# CS301_YOURGROUPNUM.net
KiCad netlist of a schematic drawn in Altium Designer
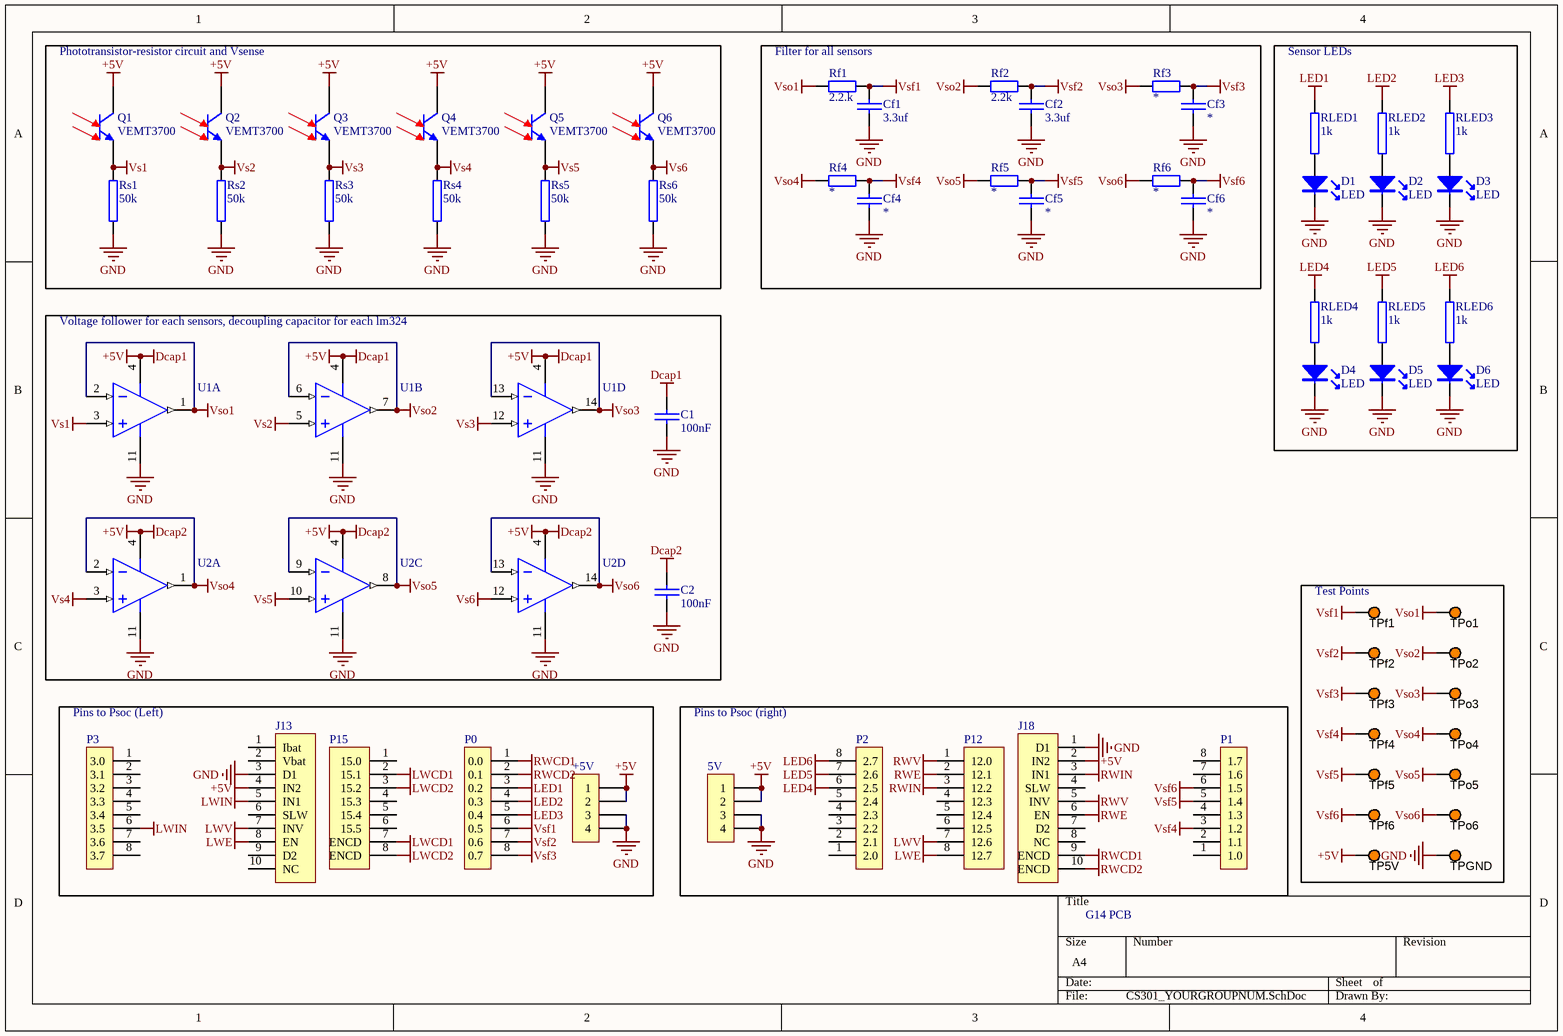
[diagram p0: CS301_YOURGROUPNUM.SchDoc]

(export (version "E")
  (design (tool "Eeschema 10.0.6"))
  (components
    (comp (ref "+5V")
      (value "5V")
      (footprint "IDC4")
      (description "Connector")
      (libsource (lib "Miscellaneous Devices") (part "CON4"))
    )
    (comp (ref "5V")
      (value "5V")
      (footprint "IDC4")
      (description "Connector")
      (libsource (lib "Miscellaneous Devices") (part "CON4"))
    )
    (comp (ref "C1")
      (value "100nF")
      (footprint "CCAP-5P0")
      (description "TH ceramic capacitor with 5mm pitch")
      (libsource (lib "EE209_SchLib") (part "CerCap_TH_5P0"))
    )
    (comp (ref "C2")
      (value "100nF")
      (footprint "CCAP-5P0")
      (description "TH ceramic capacitor with 5mm pitch")
      (libsource (lib "EE209_SchLib") (part "CerCap_TH_5P0"))
    )
    (comp (ref "Cf1")
      (value "3.3uf")
      (footprint "CCAP-5P0")
      (description "TH ceramic capacitor with 5mm pitch")
      (libsource (lib "EE209_SchLib") (part "CerCap_TH_5P0"))
    )
    (comp (ref "Cf2")
      (value "3.3uf")
      (footprint "CCAP-5P0")
      (description "TH ceramic capacitor with 5mm pitch")
      (libsource (lib "EE209_SchLib") (part "CerCap_TH_5P0"))
    )
    (comp (ref "Cf3")
      (value "*")
      (footprint "CCAP-5P0")
      (description "TH ceramic capacitor with 5mm pitch")
      (libsource (lib "EE209_SchLib") (part "CerCap_TH_5P0"))
    )
    (comp (ref "Cf4")
      (value "*")
      (footprint "CCAP-5P0")
      (description "TH ceramic capacitor with 5mm pitch")
      (libsource (lib "EE209_SchLib") (part "CerCap_TH_5P0"))
    )
    (comp (ref "Cf5")
      (value "*")
      (footprint "CCAP-5P0")
      (description "TH ceramic capacitor with 5mm pitch")
      (libsource (lib "EE209_SchLib") (part "CerCap_TH_5P0"))
    )
    (comp (ref "Cf6")
      (value "*")
      (footprint "CCAP-5P0")
      (description "TH ceramic capacitor with 5mm pitch")
      (libsource (lib "EE209_SchLib") (part "CerCap_TH_5P0"))
    )
    (comp (ref "D1") (value "LED") (footprint "LED0.1/5MM") (libsource (lib "COMSYS301") (part "LED")))
    (comp (ref "D2") (value "LED") (footprint "LED0.1/5MM") (libsource (lib "COMSYS301") (part "LED")))
    (comp (ref "D3") (value "LED") (footprint "LED0.1/5MM") (libsource (lib "COMSYS301") (part "LED")))
    (comp (ref "D4") (value "LED") (footprint "LED0.1/5MM") (libsource (lib "COMSYS301") (part "LED")))
    (comp (ref "D5") (value "LED") (footprint "LED0.1/5MM") (libsource (lib "COMSYS301") (part "LED")))
    (comp (ref "D6") (value "LED") (footprint "LED0.1/5MM") (libsource (lib "COMSYS301") (part "LED")))
    (comp (ref "J13")
      (value "CON10")
      (footprint "idc10")
      (description "Connector")
      (libsource (lib "Miscellaneous Devices") (part "CON10"))
    )
    (comp (ref "J18")
      (value "CON10")
      (footprint "IDC10")
      (description "Connector")
      (libsource (lib "") (part "CON10_1"))
    )
    (comp (ref "P0")
      (value "P0")
      (footprint "idc8")
      (description "Connector")
      (libsource (lib "") (part "CON8_1"))
    )
    (comp (ref "P1")
      (value "P1")
      (footprint "idc8")
      (description "Connector")
      (libsource (lib "") (part "CON8_2"))
    )
    (comp (ref "P2")
      (value "P2")
      (footprint "idc8")
      (description "Connector")
      (libsource (lib "") (part "CON8_2"))
    )
    (comp (ref "P3")
      (value "P3")
      (footprint "idc8")
      (description "Connector")
      (libsource (lib "Miscellaneous Devices") (part "CON8"))
    )
    (comp (ref "P12")
      (value "P12")
      (footprint "idc8")
      (description "Connector")
      (libsource (lib "Miscellaneous Devices") (part "CON8_1"))
    )
    (comp (ref "P15")
      (value "P15")
      (footprint "idc8")
      (description "Connector")
      (libsource (lib "") (part "CON8_1_1"))
    )
    (comp (ref "Q1")
      (value "VEMT3700")
      (footprint "VEMT3700")
      (description "Silicon NPN Phototransistor")
      (libsource (lib "COMSYS301") (part "VEMT3700"))
    )
    (comp (ref "Q2")
      (value "VEMT3700")
      (footprint "VEMT3700")
      (description "Silicon NPN Phototransistor")
      (libsource (lib "COMSYS301") (part "VEMT3700"))
    )
    (comp (ref "Q3")
      (value "VEMT3700")
      (footprint "VEMT3700")
      (description "Silicon NPN Phototransistor")
      (libsource (lib "COMSYS301") (part "VEMT3700"))
    )
    (comp (ref "Q4")
      (value "VEMT3700")
      (footprint "VEMT3700")
      (description "Silicon NPN Phototransistor")
      (libsource (lib "COMSYS301") (part "VEMT3700"))
    )
    (comp (ref "Q5")
      (value "VEMT3700")
      (footprint "VEMT3700")
      (description "Silicon NPN Phototransistor")
      (libsource (lib "COMSYS301") (part "VEMT3700"))
    )
    (comp (ref "Q6")
      (value "VEMT3700")
      (footprint "VEMT3700")
      (description "Silicon NPN Phototransistor")
      (libsource (lib "COMSYS301") (part "VEMT3700"))
    )
    (comp (ref "Rf1")
      (value "2.2.k")
      (footprint "AXIAL-0.4")
      (description "Through hole resistor")
      (fields (field (name "PUBLISHER") "Altium Limited"))
      (libsource (lib "EE209_SchLib") (part "Res_TH_0AX4"))
    )
    (comp (ref "Rf2")
      (value "2.2k")
      (footprint "AXIAL-0.4")
      (description "Through hole resistor")
      (fields (field (name "PUBLISHER") "Altium Limited"))
      (libsource (lib "EE209_SchLib") (part "Res_TH_0AX4"))
    )
    (comp (ref "Rf3")
      (value "*")
      (footprint "AXIAL-0.4")
      (description "Through hole resistor")
      (fields (field (name "PUBLISHER") "Altium Limited"))
      (libsource (lib "EE209_SchLib") (part "Res_TH_0AX4"))
    )
    (comp (ref "Rf4")
      (value "*")
      (footprint "AXIAL-0.4")
      (description "Through hole resistor")
      (fields (field (name "PUBLISHER") "Altium Limited"))
      (libsource (lib "EE209_SchLib") (part "Res_TH_0AX4"))
    )
    (comp (ref "Rf5")
      (value "*")
      (footprint "AXIAL-0.4")
      (description "Through hole resistor")
      (fields (field (name "PUBLISHER") "Altium Limited"))
      (libsource (lib "EE209_SchLib") (part "Res_TH_0AX4"))
    )
    (comp (ref "Rf6")
      (value "*")
      (footprint "AXIAL-0.4")
      (description "Through hole resistor")
      (fields (field (name "PUBLISHER") "Altium Limited"))
      (libsource (lib "EE209_SchLib") (part "Res_TH_0AX4"))
    )
    (comp (ref "RLED1") (value "1k") (footprint "AXIAL0.4") (libsource (lib "COMSYS301") (part "RES2")))
    (comp (ref "RLED2") (value "1k") (footprint "AXIAL0.4") (libsource (lib "COMSYS301") (part "RES2")))
    (comp (ref "RLED3") (value "1k") (footprint "AXIAL0.4") (libsource (lib "COMSYS301") (part "RES2")))
    (comp (ref "RLED4") (value "1k") (footprint "AXIAL0.4") (libsource (lib "COMSYS301") (part "RES2")))
    (comp (ref "RLED5") (value "1k") (footprint "AXIAL0.4") (libsource (lib "COMSYS301") (part "RES2")))
    (comp (ref "RLED6") (value "1k") (footprint "AXIAL0.4") (libsource (lib "COMSYS301") (part "RES2")))
    (comp (ref "Rs1") (value "50k") (footprint "AXIAL0.4") (libsource (lib "COMSYS301") (part "RES2")))
    (comp (ref "Rs2") (value "50k") (footprint "AXIAL0.4") (libsource (lib "COMSYS301") (part "RES2")))
    (comp (ref "Rs3") (value "50k") (footprint "AXIAL0.4") (libsource (lib "COMSYS301") (part "RES2")))
    (comp (ref "Rs4") (value "50k") (footprint "AXIAL0.4") (libsource (lib "COMSYS301") (part "RES2")))
    (comp (ref "Rs5") (value "50k") (footprint "AXIAL0.4") (libsource (lib "COMSYS301") (part "RES2")))
    (comp (ref "Rs6") (value "50k") (footprint "AXIAL0.4") (libsource (lib "COMSYS301") (part "RES2")))
    (comp (ref "TP5V")
      (value "5003")
      (footprint "EE209_PcbLib:TP_TH")
      (description "Test Point, Orange, 1-Pin THD, RoHS")
      (libsource (lib "EE209_SchLib") (part "TestPoint"))
    )
    (comp (ref "TPf1")
      (value "5003")
      (footprint "EE209_PcbLib:TP_TH")
      (description "Test Point, Orange, 1-Pin THD, RoHS")
      (libsource (lib "EE209_SchLib") (part "TestPoint"))
    )
    (comp (ref "TPf2")
      (value "5003")
      (footprint "EE209_PcbLib:TP_TH")
      (description "Test Point, Orange, 1-Pin THD, RoHS")
      (libsource (lib "EE209_SchLib") (part "TestPoint"))
    )
    (comp (ref "TPf3")
      (value "5003")
      (footprint "EE209_PcbLib:TP_TH")
      (description "Test Point, Orange, 1-Pin THD, RoHS")
      (libsource (lib "EE209_SchLib") (part "TestPoint"))
    )
    (comp (ref "TPf4")
      (value "5003")
      (footprint "EE209_PcbLib:TP_TH")
      (description "Test Point, Orange, 1-Pin THD, RoHS")
      (libsource (lib "EE209_SchLib") (part "TestPoint"))
    )
    (comp (ref "TPf5")
      (value "5003")
      (footprint "EE209_PcbLib:TP_TH")
      (description "Test Point, Orange, 1-Pin THD, RoHS")
      (libsource (lib "EE209_SchLib") (part "TestPoint"))
    )
    (comp (ref "TPf6")
      (value "5003")
      (footprint "EE209_PcbLib:TP_TH")
      (description "Test Point, Orange, 1-Pin THD, RoHS")
      (libsource (lib "EE209_SchLib") (part "TestPoint"))
    )
    (comp (ref "TPGND")
      (value "5003")
      (footprint "EE209_PcbLib:TP_TH")
      (description "Test Point, Orange, 1-Pin THD, RoHS")
      (libsource (lib "EE209_SchLib") (part "TestPoint"))
    )
    (comp (ref "TPo1")
      (value "5003")
      (footprint "EE209_PcbLib:TP_TH")
      (description "Test Point, Orange, 1-Pin THD, RoHS")
      (libsource (lib "EE209_SchLib") (part "TestPoint"))
    )
    (comp (ref "TPo2")
      (value "5003")
      (footprint "EE209_PcbLib:TP_TH")
      (description "Test Point, Orange, 1-Pin THD, RoHS")
      (libsource (lib "EE209_SchLib") (part "TestPoint"))
    )
    (comp (ref "TPo3")
      (value "5003")
      (footprint "EE209_PcbLib:TP_TH")
      (description "Test Point, Orange, 1-Pin THD, RoHS")
      (libsource (lib "EE209_SchLib") (part "TestPoint"))
    )
    (comp (ref "TPo4")
      (value "5003")
      (footprint "EE209_PcbLib:TP_TH")
      (description "Test Point, Orange, 1-Pin THD, RoHS")
      (libsource (lib "EE209_SchLib") (part "TestPoint"))
    )
    (comp (ref "TPo5")
      (value "5003")
      (footprint "EE209_PcbLib:TP_TH")
      (description "Test Point, Orange, 1-Pin THD, RoHS")
      (libsource (lib "EE209_SchLib") (part "TestPoint"))
    )
    (comp (ref "TPo6")
      (value "5003")
      (footprint "EE209_PcbLib:TP_TH")
      (description "Test Point, Orange, 1-Pin THD, RoHS")
      (libsource (lib "EE209_SchLib") (part "TestPoint"))
    )
    (comp (ref "U1")
      (value "LM324")
      (footprint "DIP-14")
      (description "IC OPAMP GP 14DIP")
      (fields
        (field (name "MANUFACTURER") "ON Semiconductor")
        (field (name "MANUFACTURER PART NUMBER") "LM324N")
      )
      (libsource (lib "EE209_SchLib") (part "LM324N_TH_DIP16"))
    )
    (comp (ref "U2")
      (value "LM324")
      (footprint "DIP-14")
      (description "IC OPAMP GP 14DIP")
      (fields
        (field (name "MANUFACTURER") "ON Semiconductor")
        (field (name "MANUFACTURER PART NUMBER") "LM324N")
      )
      (libsource (lib "EE209_SchLib") (part "LM324N_TH_DIP16"))
    )
  )
  (nets
    (net (code "1") (name "+5V") (class "Default")
      (node (ref "+5V") (pin "1") (pinfunction "1_1") (pintype "passive"))
      (node (ref "+5V") (pin "2") (pinfunction "2_2") (pintype "passive"))
      (node (ref "5V") (pin "1") (pinfunction "1_1") (pintype "passive"))
      (node (ref "5V") (pin "2") (pinfunction "2_2") (pintype "passive"))
      (node (ref "C1") (pin "1") (pinfunction "1_1") (pintype "passive"))
      (node (ref "C2") (pin "1") (pinfunction "1_1") (pintype "passive"))
      (node (ref "J13") (pin "4") (pinfunction "IN2_4") (pintype "passive"))
      (node (ref "J18") (pin "2") (pinfunction "IN2_2") (pintype "passive"))
      (node (ref "Q1") (pin "1") (pinfunction "C_1") (pintype "passive"))
      (node (ref "Q2") (pin "1") (pinfunction "C_1") (pintype "passive"))
      (node (ref "Q3") (pin "1") (pinfunction "C_1") (pintype "passive"))
      (node (ref "Q4") (pin "1") (pinfunction "C_1") (pintype "passive"))
      (node (ref "Q5") (pin "1") (pinfunction "C_1") (pintype "passive"))
      (node (ref "Q6") (pin "1") (pinfunction "C_1") (pintype "passive"))
      (node (ref "TP5V") (pin "1") (pinfunction "1_1") (pintype "passive"))
      (node (ref "U1") (pin "4") (pinfunction "VDD_4") (pintype "power_in"))
      (node (ref "U2") (pin "4") (pinfunction "VDD_4") (pintype "power_in"))
    )
    (net (code "2") (name "GND") (class "Default")
      (node (ref "+5V") (pin "3") (pinfunction "3_3") (pintype "passive"))
      (node (ref "+5V") (pin "4") (pinfunction "4_4") (pintype "passive"))
      (node (ref "5V") (pin "3") (pinfunction "3_3") (pintype "passive"))
      (node (ref "5V") (pin "4") (pinfunction "4_4") (pintype "passive"))
      (node (ref "C1") (pin "2") (pinfunction "2_2") (pintype "passive"))
      (node (ref "C2") (pin "2") (pinfunction "2_2") (pintype "passive"))
      (node (ref "Cf1") (pin "2") (pinfunction "2_2") (pintype "passive"))
      (node (ref "Cf2") (pin "2") (pinfunction "2_2") (pintype "passive"))
      (node (ref "Cf3") (pin "2") (pinfunction "2_2") (pintype "passive"))
      (node (ref "Cf4") (pin "2") (pinfunction "2_2") (pintype "passive"))
      (node (ref "Cf5") (pin "2") (pinfunction "2_2") (pintype "passive"))
      (node (ref "Cf6") (pin "2") (pinfunction "2_2") (pintype "passive"))
      (node (ref "D1") (pin "K") (pinfunction "2_K") (pintype "passive"))
      (node (ref "D2") (pin "K") (pinfunction "2_K") (pintype "passive"))
      (node (ref "D3") (pin "K") (pinfunction "2_K") (pintype "passive"))
      (node (ref "D4") (pin "K") (pinfunction "2_K") (pintype "passive"))
      (node (ref "D5") (pin "K") (pinfunction "2_K") (pintype "passive"))
      (node (ref "D6") (pin "K") (pinfunction "2_K") (pintype "passive"))
      (node (ref "J13") (pin "3") (pinfunction "D1_3") (pintype "passive"))
      (node (ref "J18") (pin "1") (pinfunction "D1_1") (pintype "passive"))
      (node (ref "Rs1") (pin "2") (pinfunction "2_2") (pintype "passive"))
      (node (ref "Rs2") (pin "2") (pinfunction "2_2") (pintype "passive"))
      (node (ref "Rs3") (pin "2") (pinfunction "2_2") (pintype "passive"))
      (node (ref "Rs4") (pin "2") (pinfunction "2_2") (pintype "passive"))
      (node (ref "Rs5") (pin "2") (pinfunction "2_2") (pintype "passive"))
      (node (ref "Rs6") (pin "2") (pinfunction "2_2") (pintype "passive"))
      (node (ref "TPGND") (pin "1") (pinfunction "1_1") (pintype "passive"))
      (node (ref "U1") (pin "11") (pinfunction "VSS_11") (pintype "power_in"))
      (node (ref "U2") (pin "11") (pinfunction "VSS_11") (pintype "power_in"))
    )
    (net (code "3") (name "LED1") (class "Default")
      (node (ref "P0") (pin "3") (pinfunction "0.2_3") (pintype "passive"))
      (node (ref "RLED1") (pin "1") (pinfunction "1_1") (pintype "passive"))
    )
    (net (code "4") (name "LED2") (class "Default")
      (node (ref "P0") (pin "4") (pinfunction "0.3_4") (pintype "passive"))
      (node (ref "RLED2") (pin "1") (pinfunction "1_1") (pintype "passive"))
    )
    (net (code "5") (name "LED3") (class "Default")
      (node (ref "P0") (pin "5") (pinfunction "0.4_5") (pintype "passive"))
      (node (ref "RLED3") (pin "1") (pinfunction "1_1") (pintype "passive"))
    )
    (net (code "6") (name "LED4") (class "Default")
      (node (ref "P2") (pin "6") (pinfunction "2.5_6") (pintype "passive"))
      (node (ref "RLED4") (pin "1") (pinfunction "1_1") (pintype "passive"))
    )
    (net (code "7") (name "LED5") (class "Default")
      (node (ref "P2") (pin "7") (pinfunction "2.6_7") (pintype "passive"))
      (node (ref "RLED5") (pin "1") (pinfunction "1_1") (pintype "passive"))
    )
    (net (code "8") (name "LED6") (class "Default")
      (node (ref "P2") (pin "8") (pinfunction "2.7_8") (pintype "passive"))
      (node (ref "RLED6") (pin "1") (pinfunction "1_1") (pintype "passive"))
    )
    (net (code "9") (name "LWCD1") (class "Default")
      (node (ref "P15") (pin "2") (pinfunction "15.1_2") (pintype "passive"))
      (node (ref "P15") (pin "7") (pinfunction "ENCD_7") (pintype "passive"))
    )
    (net (code "10") (name "LWCD2") (class "Default")
      (node (ref "P15") (pin "3") (pinfunction "15.2_3") (pintype "passive"))
      (node (ref "P15") (pin "8") (pinfunction "ENCD_8") (pintype "passive"))
    )
    (net (code "11") (name "LWE") (class "Default")
      (node (ref "J13") (pin "8") (pinfunction "EN_8") (pintype "passive"))
      (node (ref "P12") (pin "8") (pinfunction "12.7_8") (pintype "passive"))
    )
    (net (code "12") (name "LWIN") (class "Default")
      (node (ref "J13") (pin "5") (pinfunction "IN1_5") (pintype "passive"))
      (node (ref "P3") (pin "6") (pinfunction "3.5_6") (pintype "passive"))
    )
    (net (code "13") (name "LWV") (class "Default")
      (node (ref "J13") (pin "7") (pinfunction "INV_7") (pintype "passive"))
      (node (ref "P12") (pin "7") (pinfunction "12.6_7") (pintype "passive"))
    )
    (net (code "14") (name "Net-(D1-1)") (class "Default")
      (node (ref "D1") (pin "A") (pinfunction "1_A") (pintype "passive"))
      (node (ref "RLED1") (pin "2") (pinfunction "2_2") (pintype "passive"))
    )
    (net (code "15") (name "Net-(D2-1)") (class "Default")
      (node (ref "D2") (pin "A") (pinfunction "1_A") (pintype "passive"))
      (node (ref "RLED2") (pin "2") (pinfunction "2_2") (pintype "passive"))
    )
    (net (code "16") (name "Net-(D3-1)") (class "Default")
      (node (ref "D3") (pin "A") (pinfunction "1_A") (pintype "passive"))
      (node (ref "RLED3") (pin "2") (pinfunction "2_2") (pintype "passive"))
    )
    (net (code "17") (name "Net-(D4-1)") (class "Default")
      (node (ref "D4") (pin "A") (pinfunction "1_A") (pintype "passive"))
      (node (ref "RLED4") (pin "2") (pinfunction "2_2") (pintype "passive"))
    )
    (net (code "18") (name "Net-(D5-1)") (class "Default")
      (node (ref "D5") (pin "A") (pinfunction "1_A") (pintype "passive"))
      (node (ref "RLED5") (pin "2") (pinfunction "2_2") (pintype "passive"))
    )
    (net (code "19") (name "Net-(D6-1)") (class "Default")
      (node (ref "D6") (pin "A") (pinfunction "1_A") (pintype "passive"))
      (node (ref "RLED6") (pin "2") (pinfunction "2_2") (pintype "passive"))
    )
    (net (code "20") (name "RWCD1") (class "Default")
      (node (ref "J18") (pin "9") (pinfunction "ENCD_9") (pintype "passive"))
      (node (ref "P0") (pin "1") (pinfunction "0.0_1") (pintype "passive"))
    )
    (net (code "21") (name "RWCD2") (class "Default")
      (node (ref "J18") (pin "10") (pinfunction "ENCD_10") (pintype "passive"))
      (node (ref "P0") (pin "2") (pinfunction "0.1_2") (pintype "passive"))
    )
    (net (code "22") (name "RWE") (class "Default")
      (node (ref "J18") (pin "6") (pinfunction "EN_6") (pintype "passive"))
      (node (ref "P12") (pin "2") (pinfunction "12.1_2") (pintype "passive"))
    )
    (net (code "23") (name "RWIN") (class "Default")
      (node (ref "J18") (pin "3") (pinfunction "IN1_3") (pintype "passive"))
      (node (ref "P12") (pin "3") (pinfunction "12.2_3") (pintype "passive"))
    )
    (net (code "24") (name "RWV") (class "Default")
      (node (ref "J18") (pin "5") (pinfunction "INV_5") (pintype "passive"))
      (node (ref "P12") (pin "1") (pinfunction "12.0_1") (pintype "passive"))
    )
    (net (code "25") (name "Vs1") (class "Default")
      (node (ref "Q1") (pin "2") (pinfunction "E_2") (pintype "passive"))
      (node (ref "Rs1") (pin "1") (pinfunction "1_1") (pintype "passive"))
      (node (ref "U1") (pin "3") (pinfunction "VINA+_3") (pintype "input"))
    )
    (net (code "26") (name "Vs2") (class "Default")
      (node (ref "Q2") (pin "2") (pinfunction "E_2") (pintype "passive"))
      (node (ref "Rs2") (pin "1") (pinfunction "1_1") (pintype "passive"))
      (node (ref "U1") (pin "5") (pinfunction "VINB+_5") (pintype "input"))
    )
    (net (code "27") (name "Vs3") (class "Default")
      (node (ref "Q3") (pin "2") (pinfunction "E_2") (pintype "passive"))
      (node (ref "Rs3") (pin "1") (pinfunction "1_1") (pintype "passive"))
      (node (ref "U1") (pin "12") (pinfunction "VIND+_12") (pintype "input"))
    )
    (net (code "28") (name "Vs4") (class "Default")
      (node (ref "Q4") (pin "2") (pinfunction "E_2") (pintype "passive"))
      (node (ref "Rs4") (pin "1") (pinfunction "1_1") (pintype "passive"))
      (node (ref "U2") (pin "3") (pinfunction "VINA+_3") (pintype "input"))
    )
    (net (code "29") (name "Vs5") (class "Default")
      (node (ref "Q5") (pin "2") (pinfunction "E_2") (pintype "passive"))
      (node (ref "Rs5") (pin "1") (pinfunction "1_1") (pintype "passive"))
      (node (ref "U2") (pin "10") (pinfunction "VINC+_10") (pintype "input"))
    )
    (net (code "30") (name "Vs6") (class "Default")
      (node (ref "Q6") (pin "2") (pinfunction "E_2") (pintype "passive"))
      (node (ref "Rs6") (pin "1") (pinfunction "1_1") (pintype "passive"))
      (node (ref "U2") (pin "12") (pinfunction "VIND+_12") (pintype "input"))
    )
    (net (code "31") (name "Vsf1") (class "Default")
      (node (ref "Cf1") (pin "1") (pinfunction "1_1") (pintype "passive"))
      (node (ref "P0") (pin "6") (pinfunction "0.5_6") (pintype "passive"))
      (node (ref "Rf1") (pin "2") (pinfunction "2_2") (pintype "passive"))
      (node (ref "TPf1") (pin "1") (pinfunction "1_1") (pintype "passive"))
    )
    (net (code "32") (name "Vsf2") (class "Default")
      (node (ref "Cf2") (pin "1") (pinfunction "1_1") (pintype "passive"))
      (node (ref "P0") (pin "7") (pinfunction "0.6_7") (pintype "passive"))
      (node (ref "Rf2") (pin "2") (pinfunction "2_2") (pintype "passive"))
      (node (ref "TPf2") (pin "1") (pinfunction "1_1") (pintype "passive"))
    )
    (net (code "33") (name "Vsf3") (class "Default")
      (node (ref "Cf3") (pin "1") (pinfunction "1_1") (pintype "passive"))
      (node (ref "P0") (pin "8") (pinfunction "0.7_8") (pintype "passive"))
      (node (ref "Rf3") (pin "2") (pinfunction "2_2") (pintype "passive"))
      (node (ref "TPf3") (pin "1") (pinfunction "1_1") (pintype "passive"))
    )
    (net (code "34") (name "Vsf4") (class "Default")
      (node (ref "Cf4") (pin "1") (pinfunction "1_1") (pintype "passive"))
      (node (ref "P1") (pin "3") (pinfunction "2.2_3") (pintype "passive"))
      (node (ref "Rf4") (pin "2") (pinfunction "2_2") (pintype "passive"))
      (node (ref "TPf4") (pin "1") (pinfunction "1_1") (pintype "passive"))
    )
    (net (code "35") (name "Vsf5") (class "Default")
      (node (ref "Cf5") (pin "1") (pinfunction "1_1") (pintype "passive"))
      (node (ref "P1") (pin "5") (pinfunction "2.4_5") (pintype "passive"))
      (node (ref "Rf5") (pin "2") (pinfunction "2_2") (pintype "passive"))
      (node (ref "TPf5") (pin "1") (pinfunction "1_1") (pintype "passive"))
    )
    (net (code "36") (name "Vsf6") (class "Default")
      (node (ref "Cf6") (pin "1") (pinfunction "1_1") (pintype "passive"))
      (node (ref "P1") (pin "6") (pinfunction "2.5_6") (pintype "passive"))
      (node (ref "Rf6") (pin "2") (pinfunction "2_2") (pintype "passive"))
      (node (ref "TPf6") (pin "1") (pinfunction "1_1") (pintype "passive"))
    )
    (net (code "37") (name "Vso1") (class "Default")
      (node (ref "Rf1") (pin "1") (pinfunction "1_1") (pintype "passive"))
      (node (ref "TPo1") (pin "1") (pinfunction "1_1") (pintype "passive"))
      (node (ref "U1") (pin "1") (pinfunction "VOUTA_1") (pintype "output"))
      (node (ref "U1") (pin "2") (pinfunction "VINA-_2") (pintype "input"))
    )
    (net (code "38") (name "Vso2") (class "Default")
      (node (ref "Rf2") (pin "1") (pinfunction "1_1") (pintype "passive"))
      (node (ref "TPo2") (pin "1") (pinfunction "1_1") (pintype "passive"))
      (node (ref "U1") (pin "6") (pinfunction "VINB-_6") (pintype "input"))
      (node (ref "U1") (pin "7") (pinfunction "VOUTB_7") (pintype "output"))
    )
    (net (code "39") (name "Vso3") (class "Default")
      (node (ref "Rf3") (pin "1") (pinfunction "1_1") (pintype "passive"))
      (node (ref "TPo3") (pin "1") (pinfunction "1_1") (pintype "passive"))
      (node (ref "U1") (pin "13") (pinfunction "VIND-_13") (pintype "input"))
      (node (ref "U1") (pin "14") (pinfunction "VOUTD_14") (pintype "output"))
    )
    (net (code "40") (name "Vso4") (class "Default")
      (node (ref "Rf4") (pin "1") (pinfunction "1_1") (pintype "passive"))
      (node (ref "TPo4") (pin "1") (pinfunction "1_1") (pintype "passive"))
      (node (ref "U2") (pin "1") (pinfunction "VOUTA_1") (pintype "output"))
      (node (ref "U2") (pin "2") (pinfunction "VINA-_2") (pintype "input"))
    )
    (net (code "41") (name "Vso5") (class "Default")
      (node (ref "Rf5") (pin "1") (pinfunction "1_1") (pintype "passive"))
      (node (ref "TPo5") (pin "1") (pinfunction "1_1") (pintype "passive"))
      (node (ref "U2") (pin "8") (pinfunction "VOUTC_8") (pintype "output"))
      (node (ref "U2") (pin "9") (pinfunction "VINC-_9") (pintype "input"))
    )
    (net (code "42") (name "Vso6") (class "Default")
      (node (ref "Rf6") (pin "1") (pinfunction "1_1") (pintype "passive"))
      (node (ref "TPo6") (pin "1") (pinfunction "1_1") (pintype "passive"))
      (node (ref "U2") (pin "13") (pinfunction "VIND-_13") (pintype "input"))
      (node (ref "U2") (pin "14") (pinfunction "VOUTD_14") (pintype "output"))
    )
    (net (code "43") (name "unconnected-(J13-D2-Pad9)") (class "Default")
      (node (ref "J13") (pin "9") (pinfunction "D2_9") (pintype "passive"))
    )
    (net (code "44") (name "unconnected-(J13-Ibat-Pad1)") (class "Default")
      (node (ref "J13") (pin "1") (pinfunction "Ibat_1") (pintype "passive"))
    )
    (net (code "45") (name "unconnected-(J13-NC-Pad10)") (class "Default")
      (node (ref "J13") (pin "10") (pinfunction "NC_10") (pintype "passive"))
    )
    (net (code "46") (name "unconnected-(J13-SLW-Pad6)") (class "Default")
      (node (ref "J13") (pin "6") (pinfunction "SLW_6") (pintype "passive"))
    )
    (net (code "47") (name "unconnected-(J13-Vbat-Pad2)") (class "Default")
      (node (ref "J13") (pin "2") (pinfunction "Vbat_2") (pintype "passive"))
    )
    (net (code "48") (name "unconnected-(J18-D2-Pad7)") (class "Default")
      (node (ref "J18") (pin "7") (pinfunction "D2_7") (pintype "passive"))
    )
    (net (code "49") (name "unconnected-(J18-NC-Pad8)") (class "Default")
      (node (ref "J18") (pin "8") (pinfunction "NC_8") (pintype "passive"))
    )
    (net (code "50") (name "unconnected-(J18-SLW-Pad4)") (class "Default")
      (node (ref "J18") (pin "4") (pinfunction "SLW_4") (pintype "passive"))
    )
    (net (code "51") (name "unconnected-(P1-2.0-Pad1)") (class "Default")
      (node (ref "P1") (pin "1") (pinfunction "2.0_1") (pintype "passive"))
    )
    (net (code "52") (name "unconnected-(P1-2.1-Pad2)") (class "Default")
      (node (ref "P1") (pin "2") (pinfunction "2.1_2") (pintype "passive"))
    )
    (net (code "53") (name "unconnected-(P1-2.3-Pad4)") (class "Default")
      (node (ref "P1") (pin "4") (pinfunction "2.3_4") (pintype "passive"))
    )
    (net (code "54") (name "unconnected-(P1-2.6-Pad7)") (class "Default")
      (node (ref "P1") (pin "7") (pinfunction "2.6_7") (pintype "passive"))
    )
    (net (code "55") (name "unconnected-(P1-2.7-Pad8)") (class "Default")
      (node (ref "P1") (pin "8") (pinfunction "2.7_8") (pintype "passive"))
    )
    (net (code "56") (name "unconnected-(P2-2.0-Pad1)") (class "Default")
      (node (ref "P2") (pin "1") (pinfunction "2.0_1") (pintype "passive"))
    )
    (net (code "57") (name "unconnected-(P2-2.1-Pad2)") (class "Default")
      (node (ref "P2") (pin "2") (pinfunction "2.1_2") (pintype "passive"))
    )
    (net (code "58") (name "unconnected-(P2-2.2-Pad3)") (class "Default")
      (node (ref "P2") (pin "3") (pinfunction "2.2_3") (pintype "passive"))
    )
    (net (code "59") (name "unconnected-(P2-2.3-Pad4)") (class "Default")
      (node (ref "P2") (pin "4") (pinfunction "2.3_4") (pintype "passive"))
    )
    (net (code "60") (name "unconnected-(P2-2.4-Pad5)") (class "Default")
      (node (ref "P2") (pin "5") (pinfunction "2.4_5") (pintype "passive"))
    )
    (net (code "61") (name "unconnected-(P3-3.0-Pad1)") (class "Default")
      (node (ref "P3") (pin "1") (pinfunction "3.0_1") (pintype "passive"))
    )
    (net (code "62") (name "unconnected-(P3-3.1-Pad2)") (class "Default")
      (node (ref "P3") (pin "2") (pinfunction "3.1_2") (pintype "passive"))
    )
    (net (code "63") (name "unconnected-(P3-3.2-Pad3)") (class "Default")
      (node (ref "P3") (pin "3") (pinfunction "3.2_3") (pintype "passive"))
    )
    (net (code "64") (name "unconnected-(P3-3.3-Pad4)") (class "Default")
      (node (ref "P3") (pin "4") (pinfunction "3.3_4") (pintype "passive"))
    )
    (net (code "65") (name "unconnected-(P3-3.4-Pad5)") (class "Default")
      (node (ref "P3") (pin "5") (pinfunction "3.4_5") (pintype "passive"))
    )
    (net (code "66") (name "unconnected-(P3-3.6-Pad7)") (class "Default")
      (node (ref "P3") (pin "7") (pinfunction "3.6_7") (pintype "passive"))
    )
    (net (code "67") (name "unconnected-(P3-3.7-Pad8)") (class "Default")
      (node (ref "P3") (pin "8") (pinfunction "3.7_8") (pintype "passive"))
    )
    (net (code "68") (name "unconnected-(P12-12.3-Pad4)") (class "Default")
      (node (ref "P12") (pin "4") (pinfunction "12.3_4") (pintype "passive"))
    )
    (net (code "69") (name "unconnected-(P12-12.4-Pad5)") (class "Default")
      (node (ref "P12") (pin "5") (pinfunction "12.4_5") (pintype "passive"))
    )
    (net (code "70") (name "unconnected-(P12-12.5-Pad6)") (class "Default")
      (node (ref "P12") (pin "6") (pinfunction "12.5_6") (pintype "passive"))
    )
    (net (code "71") (name "unconnected-(P15-15.0-Pad1)") (class "Default")
      (node (ref "P15") (pin "1") (pinfunction "15.0_1") (pintype "passive"))
    )
    (net (code "72") (name "unconnected-(P15-15.3-Pad4)") (class "Default")
      (node (ref "P15") (pin "4") (pinfunction "15.3_4") (pintype "passive"))
    )
    (net (code "73") (name "unconnected-(P15-15.4-Pad5)") (class "Default")
      (node (ref "P15") (pin "5") (pinfunction "15.4_5") (pintype "passive"))
    )
    (net (code "74") (name "unconnected-(P15-15.5-Pad6)") (class "Default")
      (node (ref "P15") (pin "6") (pinfunction "15.5_6") (pintype "passive"))
    )
  )
)
